# power-v29.net
KiCad netlist of a schematic drawn in Altium Designer
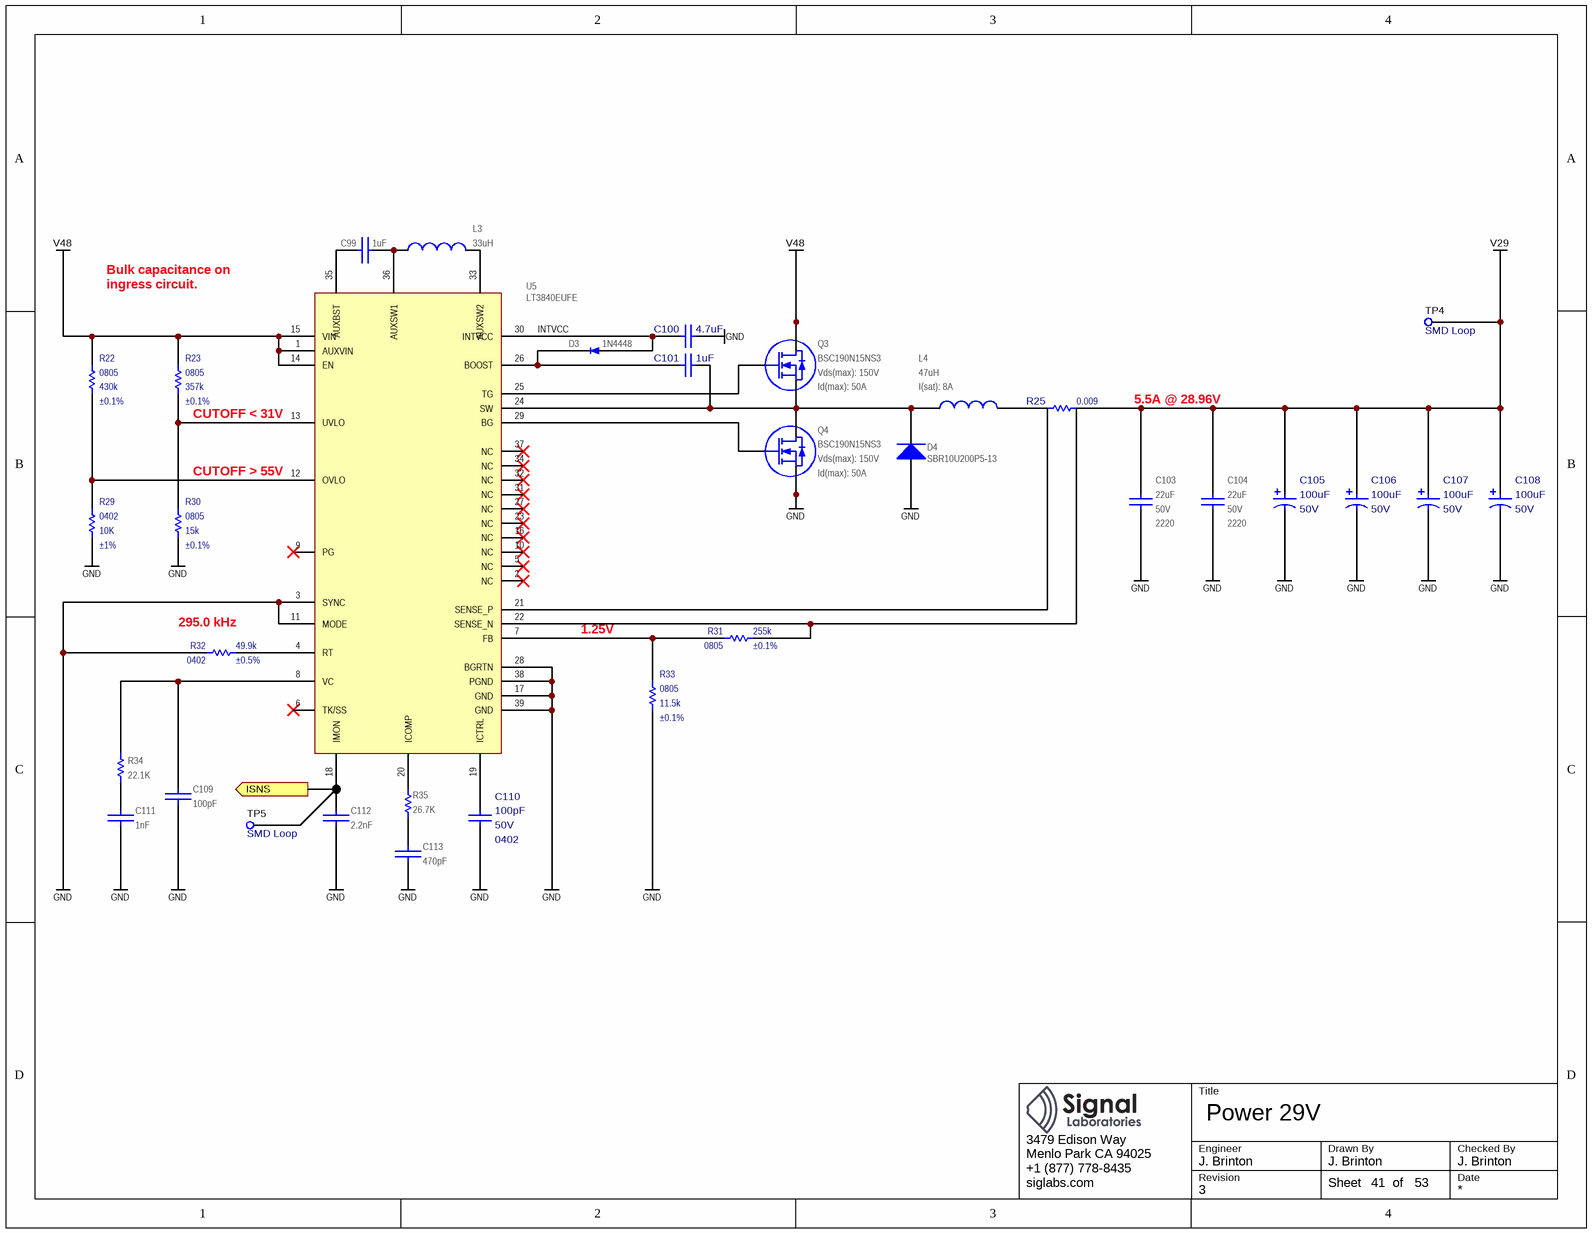
[diagram p0: power-v29.SchDoc]

(export (version "E")
  (design (tool "Eeschema 10.0.6"))
  (components
    (comp (ref "C99")
      (value "1uF")
      (footprint "CAPC100X50X55L25N")
      (description "Ceramic Capacitor 1uF ±10% 10V X5R 0402")
      (fields (field (name "MANUFACTURER") "Murata") (field (name "TOLERANCE") "±10%"))
      (libsource (lib "*") (part "CAP"))
    )
    (comp (ref "C100")
      (value "4.7uF")
      (footprint "CAPC160X80X90L20N")
      (description "Ceramic Capacitor 4.7uF ±10% 25V X5R 0603")
      (fields (field (name "MANUFACTURER") "Samsung") (field (name "TOLERANCE") "±10%"))
      (libsource (lib "capacitors") (part "CAP"))
    )
    (comp (ref "C101")
      (value "1uF")
      (footprint "CAPC100X50X55L25N")
      (description "Ceramic Capacitor 1uF ±10% 10V X5R 0402")
      (fields (field (name "MANUFACTURER") "Murata") (field (name "TOLERANCE") "±10%"))
      (libsource (lib "capacitors") (part "CAP"))
    )
    (comp (ref "C103")
      (value "22uF")
      (footprint "CAPC600X500X500L160N")
      (description "Ceramic Capacitor 22uF ±20% 50V X7S Stacked")
      (fields
        (field (name "MANUFACTURER") "TDK")
        (field (name "TOLERANCE") "±20%")
        (field (name "VOLTAGE") "50V")
        (field (name "PACKAGE") "2220")
      )
      (libsource (lib "generic") (part "CAP"))
    )
    (comp (ref "C104")
      (value "22uF")
      (footprint "CAPC600X500X500L160N")
      (description "Ceramic Capacitor 22uF ±20% 50V X7S Stacked")
      (fields
        (field (name "MANUFACTURER") "TDK")
        (field (name "TOLERANCE") "±20%")
        (field (name "VOLTAGE") "50V")
        (field (name "PACKAGE") "2220")
      )
      (libsource (lib "generic") (part "CAP"))
    )
    (comp (ref "C105")
      (value "100uF")
      (footprint "panasonic-ecg:CAPAE660X800D700L260X65N")
      (description "Aluminum Electrolytic Capacitor 100uF ±20% 50V")
      (fields
        (field (name "MANUFACTURER") "Panasonic")
        (field (name "TOLERANCE") "±20%")
        (field (name "VOLTAGE") "50V")
      )
      (libsource (lib "avx") (part "CAP_POL"))
    )
    (comp (ref "C106")
      (value "100uF")
      (footprint "panasonic-ecg:CAPAE660X800D700L260X65N")
      (description "Aluminum Electrolytic Capacitor 100uF ±20% 50V")
      (fields
        (field (name "MANUFACTURER") "Panasonic")
        (field (name "TOLERANCE") "±20%")
        (field (name "VOLTAGE") "50V")
      )
      (libsource (lib "avx") (part "CAP_POL"))
    )
    (comp (ref "C107")
      (value "100uF")
      (footprint "panasonic-ecg:CAPAE660X800D700L260X65N")
      (description "Aluminum Electrolytic Capacitor 100uF ±20% 50V")
      (fields
        (field (name "MANUFACTURER") "Panasonic")
        (field (name "TOLERANCE") "±20%")
        (field (name "VOLTAGE") "50V")
      )
      (libsource (lib "avx") (part "CAP_POL"))
    )
    (comp (ref "C108")
      (value "100uF")
      (footprint "panasonic-ecg:CAPAE660X800D700L260X65N")
      (description "Aluminum Electrolytic Capacitor 100uF ±20% 50V")
      (fields
        (field (name "MANUFACTURER") "Panasonic")
        (field (name "TOLERANCE") "±20%")
        (field (name "VOLTAGE") "50V")
      )
      (libsource (lib "avx") (part "CAP_POL"))
    )
    (comp (ref "C109")
      (value "100pF")
      (footprint "CAPC100X50X55L25N")
      (description "Ceramic Capacitor 100pF ±5% 50V NP0 0402")
      (fields (field (name "MANUFACTURER") "Murata") (field (name "VOLTAGE") "50V"))
      (libsource (lib "*") (part "CAP"))
    )
    (comp (ref "C110")
      (value "100pF")
      (footprint "generic:CAPC100X50X55L25N")
      (description "Ceramic Capacitor 100pF ±10% 50V C0G 0402")
      (fields
        (field (name "MANUFACTURER") "Vishay")
        (field (name "TOLERANCE") "±10%")
        (field (name "PACKAGE") "0402")
        (field (name "VOLTAGE") "50V")
      )
      (libsource (lib "capacitors") (part "CAP"))
    )
    (comp (ref "C111")
      (value "1nF")
      (footprint "CAPC100X50X55L25N")
      (description "Ceramic Capacitor 1nF ±5% 50V NP0 0402")
      (fields (field (name "MANUFACTURER") "Murata") (field (name "VOLTAGE") "50V"))
      (libsource (lib "*") (part "CAP"))
    )
    (comp (ref "C112")
      (value "2.2nF")
      (footprint "CAPC100X50X55L25N")
      (description "Ceramic Capacitor 2.2nF ±5% 25V NP0 0402")
      (fields (field (name "MANUFACTURER") "Kemet") (field (name "TOLERANCE") "±5%"))
      (libsource (lib "*") (part "CAP"))
    )
    (comp (ref "C113")
      (value "470pF")
      (footprint "CAPC100X50X55L25N")
      (description "Ceramic Capacitor 470pF ±5% 50V X7R 0402")
      (fields (field (name "MANUFACTURER") "Murata") (field (name "VOLTAGE") "50V"))
      (libsource (lib "*") (part "CAP"))
    )
    (comp (ref "D3")
      (value "1N4448HWS-7-F")
      (footprint "diodes_inc:SOD323")
      (description "Schottky Diode 80V 250mA SOD323")
      (fields (field (name "MANUFACTURER") "Diodes Inc") (field (name "ALTERNATIVE P/N") "1N4448"))
      (libsource (lib "diodes_inc") (part "1N4448HWS-7-F"))
    )
    (comp (ref "D4")
      (value "SBR10U200P5-13")
      (footprint "DIODES_POWERDI5")
      (description "Schottky Diode 200V 10A SMD")
      (fields (field (name "MANUFACTURER") "Diodes Inc"))
      (libsource (lib "diodes_inc") (part "PDS5100H"))
    )
    (comp (ref "L3")
      (value "33uH")
      (footprint "coilcraft:ME3220")
      (description "Inductor 33uH ±10% 500mA SMD")
      (fields (field (name "MANUFACTURER") "Coilcraft") (field (name "TOLERANCE") "±10%"))
      (libsource (lib "CamBoard_Pico_70.19K") (part "COIL"))
    )
    (comp (ref "L4")
      (value "47uH")
      (footprint "cooper:HCM1A1707")
      (description "Inductor 47uH, 8A(sat), SMD")
      (fields
        (field (name "MANUFACTURER") "Eaton")
        (field (name "I(SAT)") "8A")
        (field (name "Comment") "HCM1A1707-470-R")
      )
      (libsource (lib "CamBoard_Pico_70.19K") (part "COIL"))
    )
    (comp (ref "Q3")
      (value "BSC190N15NS3")
      (footprint "TDSON-8")
      (description "MOSFET N-Channel Enhancement Mode")
      (fields
        (field (name "MANUFACTURER") "Infineon")
        (field (name "VDS(MAX)") "150V")
        (field (name "ID(MAX)") "50A")
      )
      (libsource (lib "infinion") (part "BSC190N15NS3"))
    )
    (comp (ref "Q4")
      (value "BSC190N15NS3")
      (footprint "TDSON-8")
      (description "MOSFET N-Channel Enhancement Mode")
      (fields
        (field (name "MANUFACTURER") "Infineon")
        (field (name "VDS(MAX)") "150V")
        (field (name "ID(MAX)") "50A")
      )
      (libsource (lib "infinion") (part "BSC190N15NS3"))
    )
    (comp (ref "R22")
      (value "430k")
      (footprint "RESC2012X70N")
      (description "Thin Film Resistor 430k +/-0.1% SMD 0805")
      (fields
        (field (name "TOLERANCE") "±0.1%")
        (field (name "MANUFACTURER") "Yageo")
        (field (name "PACKAGE") "0805")
        (field (name "Comment") "RT0805BRD07430KL")
      )
      (libsource (lib "generic") (part "RES"))
    )
    (comp (ref "R23")
      (value "357k")
      (footprint "RESC2012X70N")
      (description "Thin Film Resistor 357k +/-0.1% SMD 0805")
      (fields
        (field (name "TOLERANCE") "±0.1%")
        (field (name "MANUFACTURER") "Yageo")
        (field (name "PACKAGE") "0805")
        (field (name "Comment") "RT0805BRD07357KL")
      )
      (libsource (lib "generic") (part "RES"))
    )
    (comp (ref "R25")
      (value "0.009")
      (footprint "susumu:KRL3216T4")
      (description "Current Sense Resistor 9 mOhms +/-1% SMD 4-Terminal")
      (fields (field (name "TOLERANCE") "±1%") (field (name "MANUFACTURER") "Susumu"))
      (libsource (lib "susumu") (part "KRL3216T4A-M-R009-F"))
    )
    (comp (ref "R29")
      (value "10K")
      (footprint "RESC2012X70N")
      (description "Thick Film Resistor 10k ±1% 0.1W 50V 0402")
      (fields
        (field (name "TOLERANCE") "±1%")
        (field (name "MANUFACTURER") "Panasonic")
        (field (name "PACKAGE") "0402")
        (field (name "Comment") "ERJ-2RKF1002X")
      )
      (libsource (lib "generic") (part "RES"))
    )
    (comp (ref "R30")
      (value "15k")
      (footprint "RESC2012X70N")
      (description "Thin Film Resistor 15k +/-0.1% SMD 0805")
      (fields
        (field (name "TOLERANCE") "±0.1%")
        (field (name "MANUFACTURER") "Susumu")
        (field (name "PACKAGE") "0805")
        (field (name "Comment") "RG2012P-153-B-T5")
      )
      (libsource (lib "generic") (part "RES"))
    )
    (comp (ref "R31")
      (value "255k")
      (footprint "RESC2012X70N")
      (description "Thin Film Resistor 255k +/-0.1% SMD 0805")
      (fields
        (field (name "TOLERANCE") "±0.1%")
        (field (name "MANUFACTURER") "Vishay")
        (field (name "PACKAGE") "0805")
        (field (name "Comment") "PTN0805E2553BST1")
      )
      (libsource (lib "generic") (part "RES"))
    )
    (comp (ref "R32")
      (value "49.9k")
      (footprint "RESC1005X40N")
      (description "Thin Film Resistor 49.9k +/-0.5% SMD 0402")
      (fields
        (field (name "TOLERANCE") "±0.5%")
        (field (name "MANUFACTURER") "Susumu")
        (field (name "PACKAGE") "0402")
        (field (name "Comment") "RR0510P-4992-D")
      )
      (libsource (lib "generic") (part "RES"))
    )
    (comp (ref "R33")
      (value "11.5k")
      (footprint "RESC2012X70N")
      (description "Thin Film Resistor 11.5k +/-0.1% SMD 0805")
      (fields
        (field (name "TOLERANCE") "±0.1%")
        (field (name "MANUFACTURER") "Yageo")
        (field (name "PACKAGE") "0805")
        (field (name "Comment") "RT0805BRD0711K5L")
      )
      (libsource (lib "generic") (part "RES"))
    )
    (comp (ref "R34")
      (value "22.1K")
      (footprint "generic:RESC1005X40N")
      (description "Thick Film Resistor 22.1k ±1% 0402")
      (fields (field (name "MANUFACTURER") "Panasonic") (field (name "TOLERANCE") "±1%"))
      (libsource (lib "Graviton") (part "RES 0402"))
    )
    (comp (ref "R35")
      (value "26.7K")
      (footprint "generic:RESC1005X40N")
      (description "Thick Film Resistor 26.7k ±1% 0402")
      (fields (field (name "MANUFACTURER") "Panasonic") (field (name "TOLERANCE") "±1%"))
      (libsource (lib "Graviton") (part "RES 0402"))
    )
    (comp (ref "TP4")
      (value "5015")
      (footprint "keystone:5015")
      (description "Test Point SMD")
      (fields (field (name "MANUFACTURER") "Keystone") (field (name "NOTES") "SMD Loop"))
      (libsource (lib "generic") (part "TEST_POINT_SMD_50"))
    )
    (comp (ref "TP5")
      (value "5015")
      (footprint "keystone:5015")
      (description "Test Point SMD")
      (fields (field (name "MANUFACTURER") "Keystone") (field (name "NOTES") "SMD Loop"))
      (libsource (lib "generic") (part "TEST_POINT_SMD_50"))
    )
    (comp (ref "U5")
      (value "LT3840EUFE")
      (footprint "linear:QFN39P40_600X400X80L40X20T465X265N")
      (description "Synchronous Regulator Controller")
      (fields (field (name "MANUFACTURER") "Linear Technology"))
      (libsource (lib "linear") (part "LT3840EUFE"))
    )
  )
  (nets
    (net (code "1") (name "/INTVCC") (class "Default")
      (node (ref "C100") (pin "1") (pinfunction "1_1") (pintype "passive"))
      (node (ref "D3") (pin "A") (pinfunction "A_A") (pintype "passive"))
      (node (ref "U5") (pin "30") (pinfunction "INTVCC_30") (pintype "passive"))
    )
    (net (code "2") (name "/ISNS") (class "Default")
      (node (ref "C112") (pin "1") (pinfunction "1_1") (pintype "passive"))
      (node (ref "TP5") (pin "1") (pinfunction "1_1") (pintype "passive"))
      (node (ref "U5") (pin "18") (pinfunction "IMON_18") (pintype "passive"))
    )
    (net (code "3") (name "GND") (class "Default")
      (node (ref "C100") (pin "2") (pinfunction "2_2") (pintype "passive"))
      (node (ref "C103") (pin "1") (pinfunction "1_1") (pintype "passive"))
      (node (ref "C104") (pin "1") (pinfunction "1_1") (pintype "passive"))
      (node (ref "C105") (pin "2") (pinfunction "2_2") (pintype "passive"))
      (node (ref "C106") (pin "2") (pinfunction "2_2") (pintype "passive"))
      (node (ref "C107") (pin "2") (pinfunction "2_2") (pintype "passive"))
      (node (ref "C108") (pin "2") (pinfunction "2_2") (pintype "passive"))
      (node (ref "C109") (pin "1") (pinfunction "1_1") (pintype "passive"))
      (node (ref "C110") (pin "2") (pinfunction "2_2") (pintype "passive"))
      (node (ref "C111") (pin "2") (pinfunction "2_2") (pintype "passive"))
      (node (ref "C112") (pin "2") (pinfunction "2_2") (pintype "passive"))
      (node (ref "C113") (pin "1") (pinfunction "1_1") (pintype "passive"))
      (node (ref "D4") (pin "A") (pinfunction "A_A") (pintype "power_in"))
      (node (ref "Q4") (pin "1") (pinfunction "S_1") (pintype "passive"))
      (node (ref "Q4") (pin "2") (pinfunction "S_2") (pintype "passive"))
      (node (ref "Q4") (pin "3") (pinfunction "S_3") (pintype "passive"))
      (node (ref "R29") (pin "1") (pinfunction "1_1") (pintype "passive"))
      (node (ref "R30") (pin "1") (pinfunction "1_1") (pintype "passive"))
      (node (ref "R32") (pin "2") (pinfunction "2_2") (pintype "passive"))
      (node (ref "R33") (pin "1") (pinfunction "1_1") (pintype "passive"))
      (node (ref "U5") (pin "11") (pinfunction "MODE_11") (pintype "passive"))
      (node (ref "U5") (pin "17") (pinfunction "GND_17") (pintype "passive"))
      (node (ref "U5") (pin "28") (pinfunction "BGRTN_28") (pintype "passive"))
      (node (ref "U5") (pin "3") (pinfunction "SYNC_3") (pintype "passive"))
      (node (ref "U5") (pin "38") (pinfunction "PGND_38") (pintype "passive"))
      (node (ref "U5") (pin "39") (pinfunction "GND_39") (pintype "passive"))
    )
    (net (code "4") (name "Net-(C111-Pad1)") (class "Default")
      (node (ref "C111") (pin "1") (pinfunction "1_1") (pintype "passive"))
      (node (ref "R34") (pin "1") (pinfunction "1_1") (pintype "passive"))
    )
    (net (code "5") (name "Net-(C113-Pad2)") (class "Default")
      (node (ref "C113") (pin "2") (pinfunction "2_2") (pintype "passive"))
      (node (ref "R35") (pin "2") (pinfunction "2_2") (pintype "passive"))
    )
    (net (code "6") (name "Net-(L4-Pad2)") (class "Default")
      (node (ref "L4") (pin "2") (pinfunction "2_2") (pintype "passive"))
      (node (ref "R25") (pin "2") (pinfunction "2_2") (pintype "passive"))
    )
    (net (code "7") (name "Net-(Q3-G)") (class "Default")
      (node (ref "Q3") (pin "4") (pinfunction "G_4") (pintype "passive"))
      (node (ref "U5") (pin "25") (pinfunction "TG_25") (pintype "passive"))
    )
    (net (code "8") (name "Net-(Q4-G)") (class "Default")
      (node (ref "Q4") (pin "4") (pinfunction "G_4") (pintype "passive"))
      (node (ref "U5") (pin "29") (pinfunction "BG_29") (pintype "passive"))
    )
    (net (code "9") (name "Net-(U5-AUXBST)") (class "Default")
      (node (ref "C99") (pin "2") (pinfunction "2_2") (pintype "passive"))
      (node (ref "U5") (pin "35") (pinfunction "AUXBST_35") (pintype "passive"))
    )
    (net (code "10") (name "Net-(U5-AUXSW1)") (class "Default")
      (node (ref "C99") (pin "1") (pinfunction "1_1") (pintype "passive"))
      (node (ref "L3") (pin "1") (pinfunction "1_1") (pintype "passive"))
      (node (ref "U5") (pin "36") (pinfunction "AUXSW1_36") (pintype "passive"))
    )
    (net (code "11") (name "Net-(U5-AUXSW2)") (class "Default")
      (node (ref "L3") (pin "2") (pinfunction "2_2") (pintype "passive"))
      (node (ref "U5") (pin "33") (pinfunction "AUXSW2_33") (pintype "passive"))
    )
    (net (code "12") (name "Net-(U5-BOOST)") (class "Default")
      (node (ref "C101") (pin "1") (pinfunction "1_1") (pintype "passive"))
      (node (ref "D3") (pin "K") (pinfunction "K_K") (pintype "passive"))
      (node (ref "U5") (pin "26") (pinfunction "BOOST_26") (pintype "passive"))
    )
    (net (code "13") (name "Net-(U5-FB)") (class "Default")
      (node (ref "R31") (pin "2") (pinfunction "2_2") (pintype "passive"))
      (node (ref "R33") (pin "2") (pinfunction "2_2") (pintype "passive"))
      (node (ref "U5") (pin "7") (pinfunction "FB_7") (pintype "passive"))
    )
    (net (code "14") (name "Net-(U5-ICOMP)") (class "Default")
      (node (ref "R35") (pin "1") (pinfunction "1_1") (pintype "passive"))
      (node (ref "U5") (pin "20") (pinfunction "ICOMP_20") (pintype "passive"))
    )
    (net (code "15") (name "Net-(U5-ICTRL)") (class "Default")
      (node (ref "C110") (pin "1") (pinfunction "1_1") (pintype "passive"))
      (node (ref "U5") (pin "19") (pinfunction "ICTRL_19") (pintype "passive"))
    )
    (net (code "16") (name "Net-(U5-OVLO)") (class "Default")
      (node (ref "R22") (pin "1") (pinfunction "1_1") (pintype "passive"))
      (node (ref "R29") (pin "2") (pinfunction "2_2") (pintype "passive"))
      (node (ref "U5") (pin "12") (pinfunction "OVLO_12") (pintype "passive"))
    )
    (net (code "17") (name "Net-(U5-RT)") (class "Default")
      (node (ref "R32") (pin "1") (pinfunction "1_1") (pintype "passive"))
      (node (ref "U5") (pin "4") (pinfunction "RT_4") (pintype "passive"))
    )
    (net (code "18") (name "Net-(U5-SENSE_N)") (class "Default")
      (node (ref "R25") (pin "3") (pinfunction "3_3") (pintype "passive"))
      (node (ref "R31") (pin "1") (pinfunction "1_1") (pintype "passive"))
      (node (ref "U5") (pin "22") (pinfunction "SENSE_N_22") (pintype "passive"))
    )
    (net (code "19") (name "Net-(U5-SENSE_P)") (class "Default")
      (node (ref "R25") (pin "4") (pinfunction "4_4") (pintype "passive"))
      (node (ref "U5") (pin "21") (pinfunction "SENSE_P_21") (pintype "passive"))
    )
    (net (code "20") (name "Net-(U5-SW)") (class "Default")
      (node (ref "C101") (pin "2") (pinfunction "2_2") (pintype "passive"))
      (node (ref "D4") (pin "K") (pinfunction "K_K") (pintype "passive"))
      (node (ref "L4") (pin "1") (pinfunction "1_1") (pintype "passive"))
      (node (ref "Q3") (pin "1") (pinfunction "S_1") (pintype "passive"))
      (node (ref "Q3") (pin "2") (pinfunction "S_2") (pintype "passive"))
      (node (ref "Q3") (pin "3") (pinfunction "S_3") (pintype "passive"))
      (node (ref "Q4") (pin "5") (pinfunction "D_5") (pintype "passive"))
      (node (ref "Q4") (pin "6") (pinfunction "D_6") (pintype "passive"))
      (node (ref "Q4") (pin "7") (pinfunction "D_7") (pintype "passive"))
      (node (ref "Q4") (pin "8") (pinfunction "D_8") (pintype "passive"))
      (node (ref "Q4") (pin "9") (pinfunction "D_9") (pintype "passive"))
      (node (ref "U5") (pin "24") (pinfunction "SW_24") (pintype "passive"))
    )
    (net (code "21") (name "Net-(U5-UVLO)") (class "Default")
      (node (ref "R23") (pin "1") (pinfunction "1_1") (pintype "passive"))
      (node (ref "R30") (pin "2") (pinfunction "2_2") (pintype "passive"))
      (node (ref "U5") (pin "13") (pinfunction "UVLO_13") (pintype "passive"))
    )
    (net (code "22") (name "Net-(U5-VC)") (class "Default")
      (node (ref "C109") (pin "2") (pinfunction "2_2") (pintype "passive"))
      (node (ref "R34") (pin "2") (pinfunction "2_2") (pintype "passive"))
      (node (ref "U5") (pin "8") (pinfunction "VC_8") (pintype "passive"))
    )
    (net (code "23") (name "V29") (class "Default")
      (node (ref "C103") (pin "2") (pinfunction "2_2") (pintype "passive"))
      (node (ref "C104") (pin "2") (pinfunction "2_2") (pintype "passive"))
      (node (ref "C105") (pin "1") (pinfunction "1_1") (pintype "passive"))
      (node (ref "C106") (pin "1") (pinfunction "1_1") (pintype "passive"))
      (node (ref "C107") (pin "1") (pinfunction "1_1") (pintype "passive"))
      (node (ref "C108") (pin "1") (pinfunction "1_1") (pintype "passive"))
      (node (ref "R25") (pin "1") (pinfunction "1_1") (pintype "passive"))
      (node (ref "TP4") (pin "1") (pinfunction "1_1") (pintype "passive"))
    )
    (net (code "24") (name "V48") (class "Default")
      (node (ref "Q3") (pin "5") (pinfunction "D_5") (pintype "passive"))
      (node (ref "Q3") (pin "6") (pinfunction "D_6") (pintype "passive"))
      (node (ref "Q3") (pin "7") (pinfunction "D_7") (pintype "passive"))
      (node (ref "Q3") (pin "8") (pinfunction "D_8") (pintype "passive"))
      (node (ref "Q3") (pin "9") (pinfunction "D_9") (pintype "passive"))
      (node (ref "R22") (pin "2") (pinfunction "2_2") (pintype "passive"))
      (node (ref "R23") (pin "2") (pinfunction "2_2") (pintype "passive"))
      (node (ref "U5") (pin "1") (pinfunction "AUXVIN_1") (pintype "passive"))
      (node (ref "U5") (pin "14") (pinfunction "EN_14") (pintype "passive"))
      (node (ref "U5") (pin "15") (pinfunction "VIN_15") (pintype "passive"))
    )
    (net (code "25") (name "unconnected-(U5-NC-Pad2)") (class "Default")
      (node (ref "U5") (pin "2") (pinfunction "NC_2") (pintype "passive+no_connect"))
    )
    (net (code "26") (name "unconnected-(U5-NC-Pad5)") (class "Default")
      (node (ref "U5") (pin "5") (pinfunction "NC_5") (pintype "passive+no_connect"))
    )
    (net (code "27") (name "unconnected-(U5-NC-Pad10)") (class "Default")
      (node (ref "U5") (pin "10") (pinfunction "NC_10") (pintype "passive+no_connect"))
    )
    (net (code "28") (name "unconnected-(U5-NC-Pad16)") (class "Default")
      (node (ref "U5") (pin "16") (pinfunction "NC_16") (pintype "passive+no_connect"))
    )
    (net (code "29") (name "unconnected-(U5-NC-Pad23)") (class "Default")
      (node (ref "U5") (pin "23") (pinfunction "NC_23") (pintype "passive+no_connect"))
    )
    (net (code "30") (name "unconnected-(U5-NC-Pad27)") (class "Default")
      (node (ref "U5") (pin "27") (pinfunction "NC_27") (pintype "passive+no_connect"))
    )
    (net (code "31") (name "unconnected-(U5-NC-Pad31)") (class "Default")
      (node (ref "U5") (pin "31") (pinfunction "NC_31") (pintype "passive+no_connect"))
    )
    (net (code "32") (name "unconnected-(U5-NC-Pad32)") (class "Default")
      (node (ref "U5") (pin "32") (pinfunction "NC_32") (pintype "passive+no_connect"))
    )
    (net (code "33") (name "unconnected-(U5-NC-Pad34)") (class "Default")
      (node (ref "U5") (pin "34") (pinfunction "NC_34") (pintype "passive+no_connect"))
    )
    (net (code "34") (name "unconnected-(U5-NC-Pad37)") (class "Default")
      (node (ref "U5") (pin "37") (pinfunction "NC_37") (pintype "passive+no_connect"))
    )
    (net (code "35") (name "unconnected-(U5-PG-Pad9)") (class "Default")
      (node (ref "U5") (pin "9") (pinfunction "PG_9") (pintype "passive+no_connect"))
    )
    (net (code "36") (name "unconnected-(U5-TK{slash}SS-Pad6)") (class "Default")
      (node (ref "U5") (pin "6") (pinfunction "TK/SS_6") (pintype "passive+no_connect"))
    )
  )
)
